# Multimeter_Schematic.net
KiCad netlist of a schematic drawn in Altium Designer
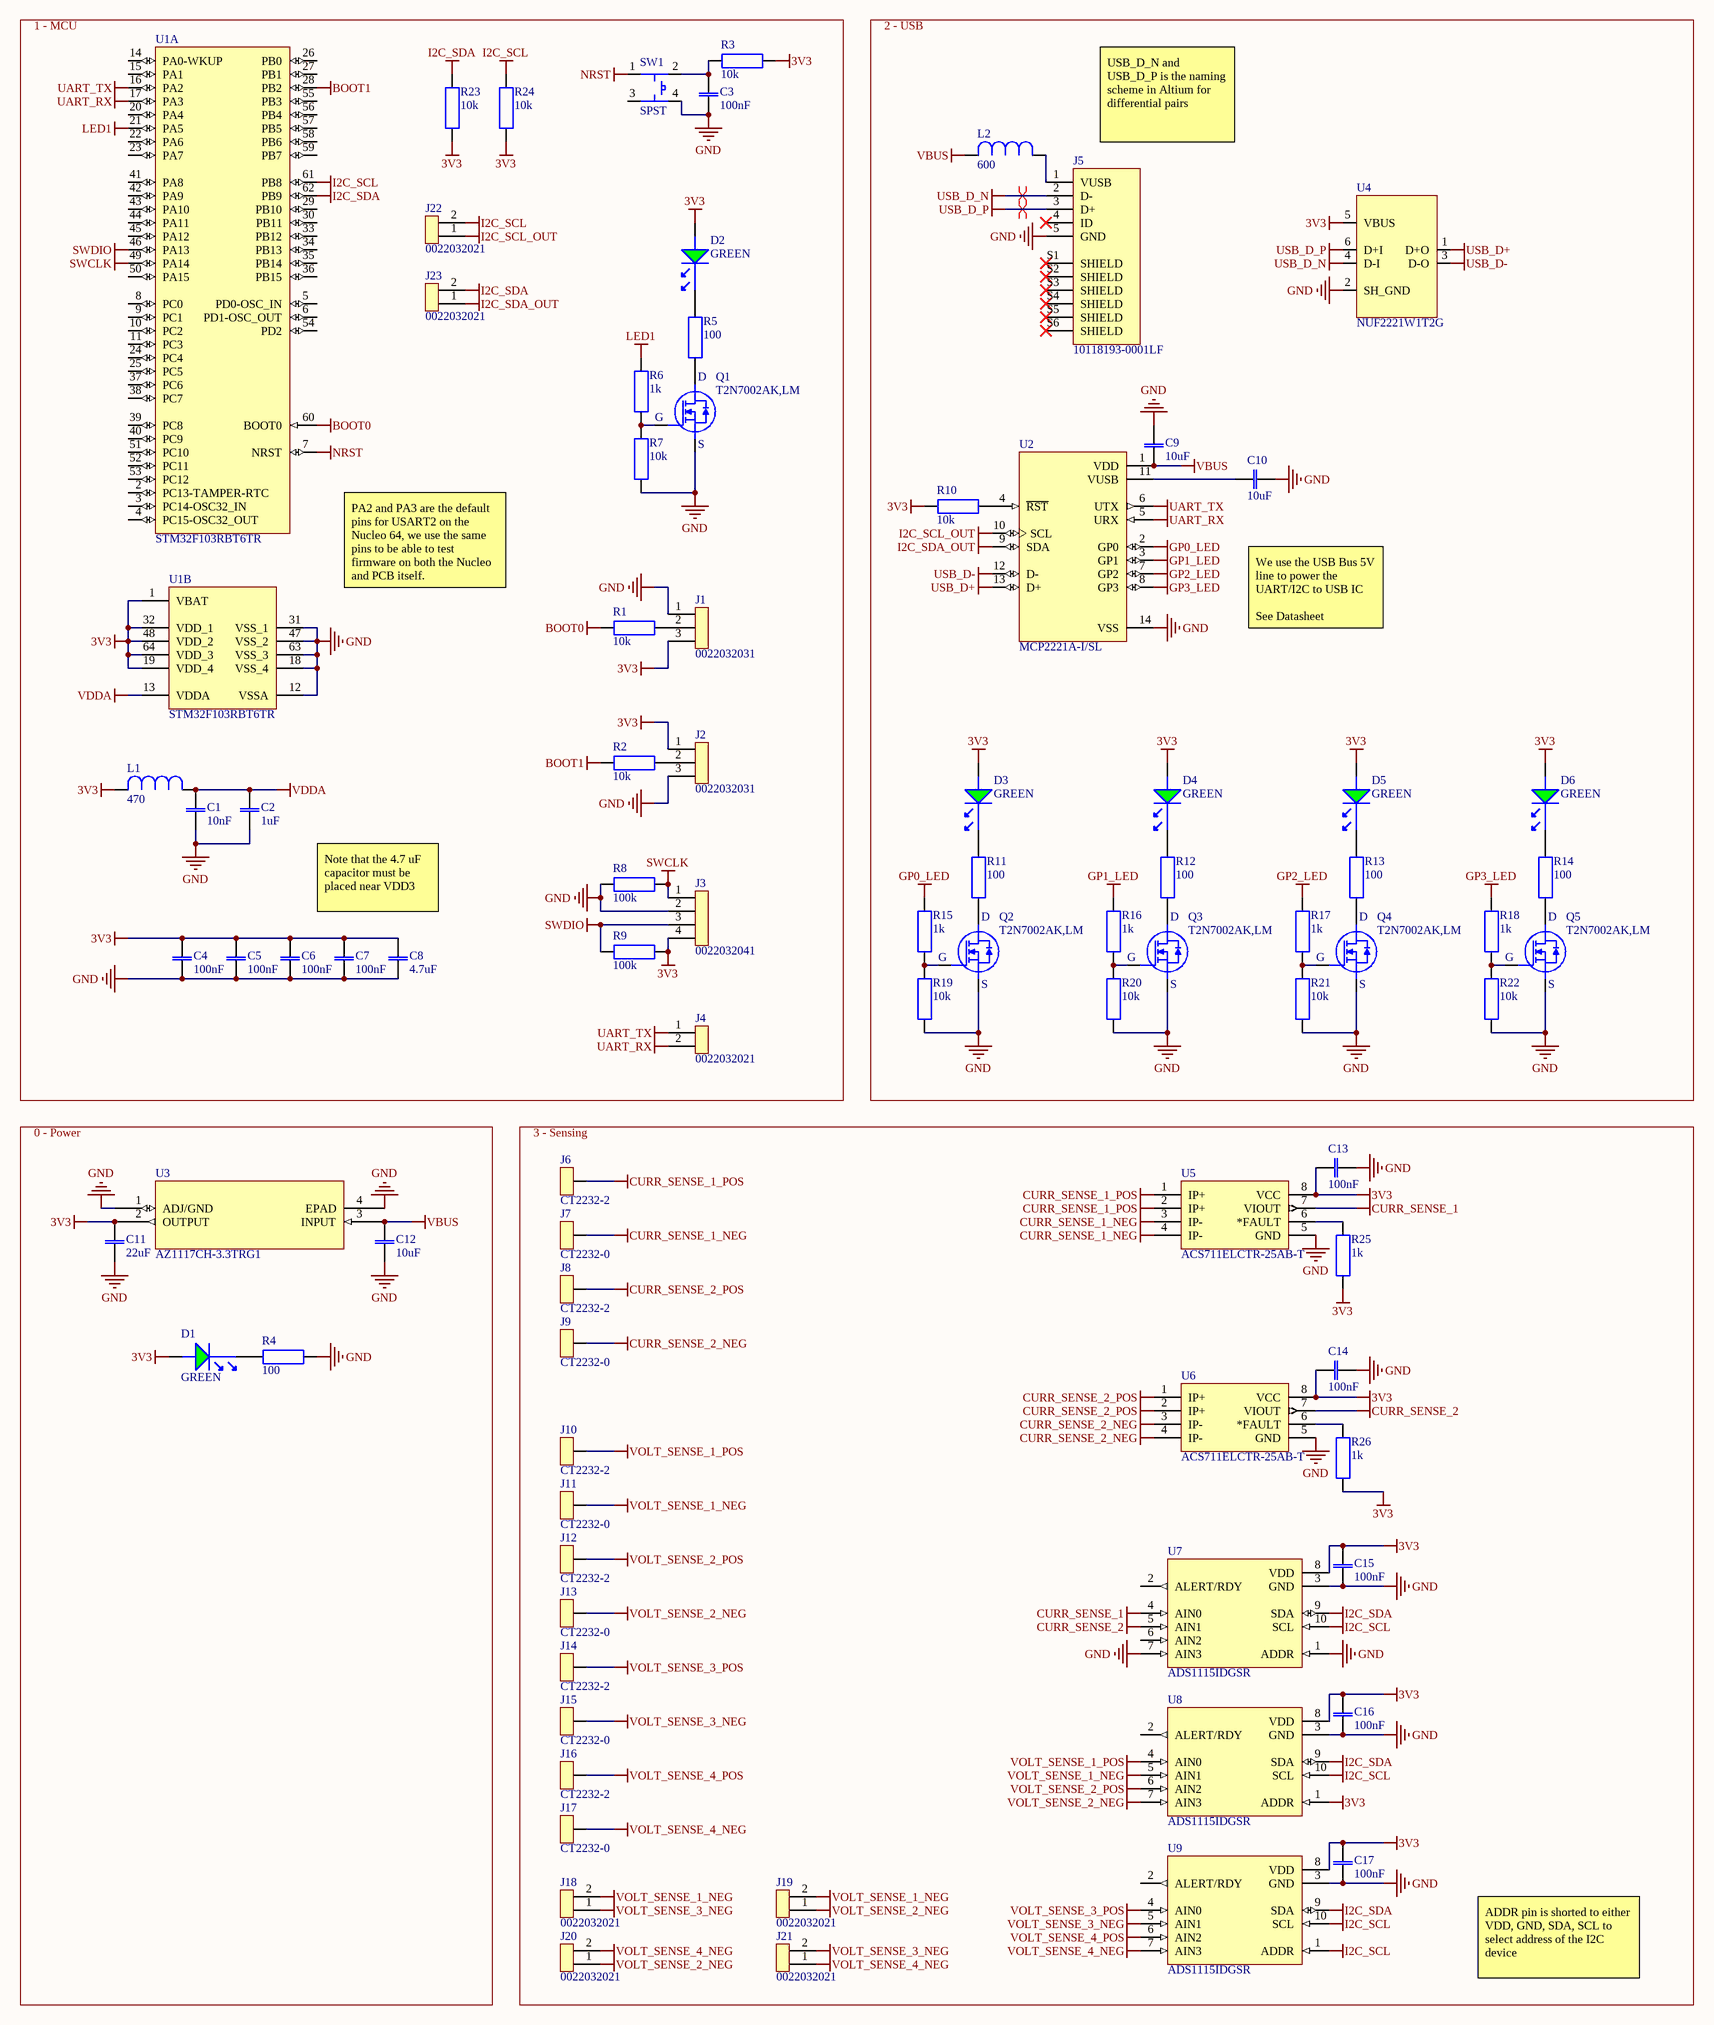
[diagram p0: Multimeter_Schematic.SchDoc]

(export (version "E")
  (design (tool "Eeschema 10.0.6"))
  (components
    (comp (ref "C1")
      (value "10nF")
      (footprint "CAP_CC0805_YAG")
      (description "10000 pF ±10% 25V Ceramic Capacitor X7R 0805 (2012 Metric)")
      (fields
        (field (name "MANUFACTURER") "YAGEO")
        (field (name "MANUFACTURER PART NUMBER") "CC0805KRX7R8BB103")
      )
      (libsource (lib "Multimeter") (part "CC0805KRX7R8BB103"))
    )
    (comp (ref "C2")
      (value "1uF")
      (footprint "CAP_CC0805_YAG")
      (description "1 µF ±10% 25V Ceramic Capacitor X7R 0805 (2012 Metric)")
      (fields
        (field (name "MANUFACTURER") "YAGEO")
        (field (name "MANUFACTURER PART NUMBER") "CC0805KKX7R8BB105")
      )
      (libsource (lib "Multimeter") (part "CC0805KKX7R8BB105"))
    )
    (comp (ref "C3")
      (value "100nF")
      (footprint "CAP_CC0805_YAG")
      (description "0.1 µF ±10% 25V Ceramic Capacitor X7R 0805 (2012 Metric)")
      (fields
        (field (name "MANUFACTURER") "YAGEO")
        (field (name "MANUFACTURER PART NUMBER") "CC0805KRX7R8BB104")
      )
      (libsource (lib "Multimeter") (part "CC0805KRX7R8BB104"))
    )
    (comp (ref "C4")
      (value "100nF")
      (footprint "CAP_CC0805_YAG")
      (description "0.1 µF ±10% 25V Ceramic Capacitor X7R 0805 (2012 Metric)")
      (fields
        (field (name "MANUFACTURER") "YAGEO")
        (field (name "MANUFACTURER PART NUMBER") "CC0805KRX7R8BB104")
      )
      (libsource (lib "Multimeter") (part "CC0805KRX7R8BB104"))
    )
    (comp (ref "C5")
      (value "100nF")
      (footprint "CAP_CC0805_YAG")
      (description "0.1 µF ±10% 25V Ceramic Capacitor X7R 0805 (2012 Metric)")
      (fields
        (field (name "MANUFACTURER") "YAGEO")
        (field (name "MANUFACTURER PART NUMBER") "CC0805KRX7R8BB104")
      )
      (libsource (lib "Multimeter") (part "CC0805KRX7R8BB104"))
    )
    (comp (ref "C6")
      (value "100nF")
      (footprint "CAP_CC0805_YAG")
      (description "0.1 µF ±10% 25V Ceramic Capacitor X7R 0805 (2012 Metric)")
      (fields
        (field (name "MANUFACTURER") "YAGEO")
        (field (name "MANUFACTURER PART NUMBER") "CC0805KRX7R8BB104")
      )
      (libsource (lib "Multimeter") (part "CC0805KRX7R8BB104"))
    )
    (comp (ref "C7")
      (value "100nF")
      (footprint "CAP_CC0805_YAG")
      (description "0.1 µF ±10% 25V Ceramic Capacitor X7R 0805 (2012 Metric)")
      (fields
        (field (name "MANUFACTURER") "YAGEO")
        (field (name "MANUFACTURER PART NUMBER") "CC0805KRX7R8BB104")
      )
      (libsource (lib "Multimeter") (part "CC0805KRX7R8BB104"))
    )
    (comp (ref "C8")
      (value "4.7uF")
      (footprint "CAP_CC0805_YAG")
      (description "4.7 µF ±10% 25V Ceramic Capacitor X7R 0805 (2012 Metric)")
      (fields
        (field (name "MANUFACTURER") "YAGEO")
        (field (name "MANUFACTURER PART NUMBER") "CC0805KKX7R8BB475")
      )
      (libsource (lib "Multimeter") (part "CC0805KKX7R8BB475"))
    )
    (comp (ref "C9")
      (value "10uF")
      (footprint "CAP_CC0805_YAG")
      (description "10 µF ±10% 25V Ceramic Capacitor X5R 0805 (2012 Metric)")
      (fields
        (field (name "MANUFACTURER") "YAGEO")
        (field (name "MANUFACTURER PART NUMBER") "CC0805KKX5R8BB106")
      )
      (libsource (lib "Multimeter") (part "CC0805KKX5R8BB106"))
    )
    (comp (ref "C10")
      (value "10uF")
      (footprint "CAP_CC0805_YAG")
      (description "10 µF ±10% 25V Ceramic Capacitor X5R 0805 (2012 Metric)")
      (fields
        (field (name "MANUFACTURER") "YAGEO")
        (field (name "MANUFACTURER PART NUMBER") "CC0805KKX5R8BB106")
      )
      (libsource (lib "Multimeter") (part "CC0805KKX5R8BB106"))
    )
    (comp (ref "C11")
      (value "22uF")
      (footprint "CAP_CC0805_YAG")
      (description "22 µF ±20% 25V Ceramic Capacitor X5R 0805 (2012 Metric)")
      (fields
        (field (name "MANUFACTURER") "YAGEO")
        (field (name "MANUFACTURER PART NUMBER") "CC0805MKX5R8BB226")
      )
      (libsource (lib "Multimeter") (part "CC0805MKX5R8BB226"))
    )
    (comp (ref "C12")
      (value "10uF")
      (footprint "CAP_CC0805_YAG")
      (description "10 µF ±10% 25V Ceramic Capacitor X5R 0805 (2012 Metric)")
      (fields
        (field (name "MANUFACTURER") "YAGEO")
        (field (name "MANUFACTURER PART NUMBER") "CC0805KKX5R8BB106")
      )
      (libsource (lib "Multimeter") (part "CC0805KKX5R8BB106"))
    )
    (comp (ref "C13")
      (value "100nF")
      (footprint "CAP_CC0805_YAG")
      (description "0.1 µF ±10% 25V Ceramic Capacitor X7R 0805 (2012 Metric)")
      (fields
        (field (name "MANUFACTURER") "YAGEO")
        (field (name "MANUFACTURER PART NUMBER") "CC0805KRX7R8BB104")
      )
      (libsource (lib "Multimeter") (part "CC0805KRX7R8BB104"))
    )
    (comp (ref "C14")
      (value "100nF")
      (footprint "CAP_CC0805_YAG")
      (description "0.1 µF ±10% 25V Ceramic Capacitor X7R 0805 (2012 Metric)")
      (fields
        (field (name "MANUFACTURER") "YAGEO")
        (field (name "MANUFACTURER PART NUMBER") "CC0805KRX7R8BB104")
      )
      (libsource (lib "Multimeter") (part "CC0805KRX7R8BB104"))
    )
    (comp (ref "C15")
      (value "100nF")
      (footprint "CAP_CC0805_YAG")
      (description "0.1 µF ±10% 25V Ceramic Capacitor X7R 0805 (2012 Metric)")
      (fields
        (field (name "MANUFACTURER") "YAGEO")
        (field (name "MANUFACTURER PART NUMBER") "CC0805KRX7R8BB104")
      )
      (libsource (lib "Multimeter") (part "CC0805KRX7R8BB104"))
    )
    (comp (ref "C16")
      (value "100nF")
      (footprint "CAP_CC0805_YAG")
      (description "0.1 µF ±10% 25V Ceramic Capacitor X7R 0805 (2012 Metric)")
      (fields
        (field (name "MANUFACTURER") "YAGEO")
        (field (name "MANUFACTURER PART NUMBER") "CC0805KRX7R8BB104")
      )
      (libsource (lib "Multimeter") (part "CC0805KRX7R8BB104"))
    )
    (comp (ref "C17")
      (value "100nF")
      (footprint "CAP_CC0805_YAG")
      (description "0.1 µF ±10% 25V Ceramic Capacitor X7R 0805 (2012 Metric)")
      (fields
        (field (name "MANUFACTURER") "YAGEO")
        (field (name "MANUFACTURER PART NUMBER") "CC0805KRX7R8BB104")
      )
      (libsource (lib "Multimeter") (part "CC0805KRX7R8BB104"))
    )
    (comp (ref "D1")
      (value "GREEN")
      (footprint "LTST-C170TGKT")
      (description "Green 525nm LED Indication - Discrete 3.2V 0805 (2012 Metric)")
      (fields
        (field (name "MANUFACTURER") "Lite-On Inc.")
        (field (name "MANUFACTURER PART NUMBER") "LTST-C170TGKT")
      )
      (libsource (lib "Multimeter") (part "LTST-C170TGKT"))
    )
    (comp (ref "D2")
      (value "GREEN")
      (footprint "LTST-C170TGKT")
      (description "Green 525nm LED Indication - Discrete 3.2V 0805 (2012 Metric)")
      (fields
        (field (name "MANUFACTURER") "Lite-On Inc.")
        (field (name "MANUFACTURER PART NUMBER") "LTST-C170TGKT")
      )
      (libsource (lib "Multimeter") (part "LTST-C170TGKT"))
    )
    (comp (ref "D3")
      (value "GREEN")
      (footprint "LTST-C170TGKT")
      (description "Green 525nm LED Indication - Discrete 3.2V 0805 (2012 Metric)")
      (fields
        (field (name "MANUFACTURER") "Lite-On Inc.")
        (field (name "MANUFACTURER PART NUMBER") "LTST-C170TGKT")
      )
      (libsource (lib "Multimeter") (part "LTST-C170TGKT"))
    )
    (comp (ref "D4")
      (value "GREEN")
      (footprint "LTST-C170TGKT")
      (description "Green 525nm LED Indication - Discrete 3.2V 0805 (2012 Metric)")
      (fields
        (field (name "MANUFACTURER") "Lite-On Inc.")
        (field (name "MANUFACTURER PART NUMBER") "LTST-C170TGKT")
      )
      (libsource (lib "Multimeter") (part "LTST-C170TGKT"))
    )
    (comp (ref "D5")
      (value "GREEN")
      (footprint "LTST-C170TGKT")
      (description "Green 525nm LED Indication - Discrete 3.2V 0805 (2012 Metric)")
      (fields
        (field (name "MANUFACTURER") "Lite-On Inc.")
        (field (name "MANUFACTURER PART NUMBER") "LTST-C170TGKT")
      )
      (libsource (lib "Multimeter") (part "LTST-C170TGKT"))
    )
    (comp (ref "D6")
      (value "GREEN")
      (footprint "LTST-C170TGKT")
      (description "Green 525nm LED Indication - Discrete 3.2V 0805 (2012 Metric)")
      (fields
        (field (name "MANUFACTURER") "Lite-On Inc.")
        (field (name "MANUFACTURER PART NUMBER") "LTST-C170TGKT")
      )
      (libsource (lib "Multimeter") (part "LTST-C170TGKT"))
    )
    (comp (ref "J1")
      (value "0022032031")
      (footprint "CONN3X1_22032031_MOL")
      (description "Connector Header Through Hole 3 position 0.100\" (2.54mm)")
      (fields (field (name "MANUFACTURER") "Molex"))
      (libsource (lib "Multimeter") (part "0022032031"))
    )
    (comp (ref "J2")
      (value "0022032031")
      (footprint "CONN3X1_22032031_MOL")
      (description "Connector Header Through Hole 3 position 0.100\" (2.54mm)")
      (fields (field (name "MANUFACTURER") "Molex"))
      (libsource (lib "Multimeter") (part "0022032031"))
    )
    (comp (ref "J3")
      (value "0022032041")
      (footprint "CONN3X1_22032041_MOL")
      (description "Connector Header Through Hole 4 position 0.100\" (2.54mm)")
      (fields (field (name "MANUFACTURER") "Molex"))
      (libsource (lib "Multimeter") (part "0022032041"))
    )
    (comp (ref "J4")
      (value "0022032021")
      (footprint "CONN3X1_22032021_MOL")
      (description "Connector Header Through Hole 2 position 0.100\" (2.54mm)")
      (fields (field (name "MANUFACTURER") "Molex"))
      (libsource (lib "Multimeter") (part "0022032021"))
    )
    (comp (ref "J5")
      (value "10118193-0001LF")
      (footprint "AMPHENOL_10118193-0001LF")
      (description "USB - micro B USB 2.0 Receptacle Connector 5 Position Surface Mount, Right Angle; Through Hole")
      (fields (field (name "MF") "Amphenol ICC") (field (name "MANUFACTURER") "Amphenol ICC (FCI)"))
      (libsource (lib "Multimeter") (part "10118193-0001LF"))
    )
    (comp (ref "J6")
      (value "CT2232-2")
      (footprint "CT2232-2")
      (description "(Banana) CONN BIND POST KNURLED RED")
      (fields (field (name "MANUFACTURER") "Cal Test Electronics"))
      (libsource (lib "Multimeter") (part "CT2232-2"))
    )
    (comp (ref "J7")
      (value "CT2232-0")
      (footprint "CT2232-0")
      (description "(Banana) CONN BIND POST KNURLED BLACK")
      (fields (field (name "MANUFACTURER") "Cal Test Electronics"))
      (libsource (lib "Multimeter") (part "CT2232-0"))
    )
    (comp (ref "J8")
      (value "CT2232-2")
      (footprint "CT2232-2")
      (description "(Banana) CONN BIND POST KNURLED RED")
      (fields (field (name "MANUFACTURER") "Cal Test Electronics"))
      (libsource (lib "Multimeter") (part "CT2232-2"))
    )
    (comp (ref "J9")
      (value "CT2232-0")
      (footprint "CT2232-0")
      (description "(Banana) CONN BIND POST KNURLED BLACK")
      (fields (field (name "MANUFACTURER") "Cal Test Electronics"))
      (libsource (lib "Multimeter") (part "CT2232-0"))
    )
    (comp (ref "J10")
      (value "CT2232-2")
      (footprint "CT2232-2")
      (description "(Banana) CONN BIND POST KNURLED RED")
      (fields (field (name "MANUFACTURER") "Cal Test Electronics"))
      (libsource (lib "Multimeter") (part "CT2232-2"))
    )
    (comp (ref "J11")
      (value "CT2232-0")
      (footprint "CT2232-0")
      (description "(Banana) CONN BIND POST KNURLED BLACK")
      (fields (field (name "MANUFACTURER") "Cal Test Electronics"))
      (libsource (lib "Multimeter") (part "CT2232-0"))
    )
    (comp (ref "J12")
      (value "CT2232-2")
      (footprint "CT2232-2")
      (description "(Banana) CONN BIND POST KNURLED RED")
      (fields (field (name "MANUFACTURER") "Cal Test Electronics"))
      (libsource (lib "Multimeter") (part "CT2232-2"))
    )
    (comp (ref "J13")
      (value "CT2232-0")
      (footprint "CT2232-0")
      (description "(Banana) CONN BIND POST KNURLED BLACK")
      (fields (field (name "MANUFACTURER") "Cal Test Electronics"))
      (libsource (lib "Multimeter") (part "CT2232-0"))
    )
    (comp (ref "J14")
      (value "CT2232-2")
      (footprint "CT2232-2")
      (description "(Banana) CONN BIND POST KNURLED RED")
      (fields (field (name "MANUFACTURER") "Cal Test Electronics"))
      (libsource (lib "Multimeter") (part "CT2232-2"))
    )
    (comp (ref "J15")
      (value "CT2232-0")
      (footprint "CT2232-0")
      (description "(Banana) CONN BIND POST KNURLED BLACK")
      (fields (field (name "MANUFACTURER") "Cal Test Electronics"))
      (libsource (lib "Multimeter") (part "CT2232-0"))
    )
    (comp (ref "J16")
      (value "CT2232-2")
      (footprint "CT2232-2")
      (description "(Banana) CONN BIND POST KNURLED RED")
      (fields (field (name "MANUFACTURER") "Cal Test Electronics"))
      (libsource (lib "Multimeter") (part "CT2232-2"))
    )
    (comp (ref "J17")
      (value "CT2232-0")
      (footprint "CT2232-0")
      (description "(Banana) CONN BIND POST KNURLED BLACK")
      (fields (field (name "MANUFACTURER") "Cal Test Electronics"))
      (libsource (lib "Multimeter") (part "CT2232-0"))
    )
    (comp (ref "J18")
      (value "0022032021")
      (footprint "CONN3X1_22032021_MOL")
      (description "Connector Header Through Hole 2 position 0.100\" (2.54mm)")
      (fields (field (name "MANUFACTURER") "Molex"))
      (libsource (lib "") (part "0022032021_1"))
    )
    (comp (ref "J19")
      (value "0022032021")
      (footprint "CONN3X1_22032021_MOL")
      (description "Connector Header Through Hole 2 position 0.100\" (2.54mm)")
      (fields (field (name "MANUFACTURER") "Molex"))
      (libsource (lib "") (part "0022032021_1"))
    )
    (comp (ref "J20")
      (value "0022032021")
      (footprint "CONN3X1_22032021_MOL")
      (description "Connector Header Through Hole 2 position 0.100\" (2.54mm)")
      (fields (field (name "MANUFACTURER") "Molex"))
      (libsource (lib "") (part "0022032021_1"))
    )
    (comp (ref "J21")
      (value "0022032021")
      (footprint "CONN3X1_22032021_MOL")
      (description "Connector Header Through Hole 2 position 0.100\" (2.54mm)")
      (fields (field (name "MANUFACTURER") "Molex"))
      (libsource (lib "") (part "0022032021_1"))
    )
    (comp (ref "J22")
      (value "0022032021")
      (footprint "CONN3X1_22032021_MOL")
      (description "Connector Header Through Hole 2 position 0.100\" (2.54mm)")
      (fields (field (name "MANUFACTURER") "Molex"))
      (libsource (lib "") (part "0022032021_1"))
    )
    (comp (ref "J23")
      (value "0022032021")
      (footprint "CONN3X1_22032021_MOL")
      (description "Connector Header Through Hole 2 position 0.100\" (2.54mm)")
      (fields (field (name "MANUFACTURER") "Molex"))
      (libsource (lib "") (part "0022032021_1"))
    )
    (comp (ref "L1")
      (value "470")
      (footprint "IND_HZ0805G471R-10")
      (description "470 Ohms @ 100 MHz 1 Power, Signal Line Ferrite Bead 0805 (2012 Metric) 1A 200mOhm")
      (fields
        (field (name "MANUFACTURER") "Laird-Signal Integrity Products")
        (field (name "MANUFACTURER PART NUMBER") "HZ0805G471R-10")
      )
      (libsource (lib "Multimeter") (part "HZ0805G471R-10"))
    )
    (comp (ref "L2")
      (value "600")
      (footprint "IND_HZ0805G471R-10")
      (description "600 Ohms @ 100 MHz 1 Power, Signal Line Ferrite Bead 0603 (1608 Metric) 1A 200mOhm")
      (fields
        (field (name "MANUFACTURER") "Laird-Signal Integrity Products")
        (field (name "MANUFACTURER PART NUMBER") "MI0603J601R-10")
      )
      (libsource (lib "Multimeter") (part "MI0603J601R-10"))
    )
    (comp (ref "Q1")
      (value "T2N7002AK,LM")
      (footprint "T2N7002AK,LM")
      (description "N-Channel 60 V 200mA (Ta) 320mW (Ta) Surface Mount SOT-23-3")
      (fields (field (name "MANUFACTURER") "Toshiba Semiconductor and Storage"))
      (libsource (lib "Multimeter") (part "T2N7002AK,LM"))
    )
    (comp (ref "Q2")
      (value "T2N7002AK,LM")
      (footprint "T2N7002AK,LM")
      (description "N-Channel 60 V 200mA (Ta) 320mW (Ta) Surface Mount SOT-23-3")
      (fields (field (name "MANUFACTURER") "Toshiba Semiconductor and Storage"))
      (libsource (lib "Multimeter") (part "T2N7002AK,LM"))
    )
    (comp (ref "Q3")
      (value "T2N7002AK,LM")
      (footprint "T2N7002AK,LM")
      (description "N-Channel 60 V 200mA (Ta) 320mW (Ta) Surface Mount SOT-23-3")
      (fields (field (name "MANUFACTURER") "Toshiba Semiconductor and Storage"))
      (libsource (lib "Multimeter") (part "T2N7002AK,LM"))
    )
    (comp (ref "Q4")
      (value "T2N7002AK,LM")
      (footprint "T2N7002AK,LM")
      (description "N-Channel 60 V 200mA (Ta) 320mW (Ta) Surface Mount SOT-23-3")
      (fields (field (name "MANUFACTURER") "Toshiba Semiconductor and Storage"))
      (libsource (lib "Multimeter") (part "T2N7002AK,LM"))
    )
    (comp (ref "Q5")
      (value "T2N7002AK,LM")
      (footprint "T2N7002AK,LM")
      (description "N-Channel 60 V 200mA (Ta) 320mW (Ta) Surface Mount SOT-23-3")
      (fields (field (name "MANUFACTURER") "Toshiba Semiconductor and Storage"))
      (libsource (lib "Multimeter") (part "T2N7002AK,LM"))
    )
    (comp (ref "R1")
      (value "10k")
      (footprint "RESC2012X60N")
      (description "10 kOhms ±1% 0.125W, 1/8W Chip Resistor 0805 (2012 Metric) Moisture Resistant Thick Film")
      (fields
        (field (name "MANUFACTURER") "YAGEO")
        (field (name "MANUFACTURER PART NUMBER") "RC0805FR-0710KL")
      )
      (libsource (lib "Multimeter") (part "RC0805FR-0710KL"))
    )
    (comp (ref "R2")
      (value "10k")
      (footprint "RESC2012X60N")
      (description "10 kOhms ±1% 0.125W, 1/8W Chip Resistor 0805 (2012 Metric) Moisture Resistant Thick Film")
      (fields
        (field (name "MANUFACTURER") "YAGEO")
        (field (name "MANUFACTURER PART NUMBER") "RC0805FR-0710KL")
      )
      (libsource (lib "Multimeter") (part "RC0805FR-0710KL"))
    )
    (comp (ref "R3")
      (value "10k")
      (footprint "RESC2012X60N")
      (description "10 kOhms ±1% 0.125W, 1/8W Chip Resistor 0805 (2012 Metric) Moisture Resistant Thick Film")
      (fields
        (field (name "MANUFACTURER") "YAGEO")
        (field (name "MANUFACTURER PART NUMBER") "RC0805FR-0710KL")
      )
      (libsource (lib "Multimeter") (part "RC0805FR-0710KL"))
    )
    (comp (ref "R4")
      (value "100")
      (footprint "RESC2012X60N")
      (description "100 Ohms ±1% 0.125W, 1/8W Chip Resistor 0805 (2012 Metric) Moisture Resistant Thick Film")
      (fields
        (field (name "MANUFACTURER") "YAGEO")
        (field (name "MANUFACTURER PART NUMBER") "RC0805FR-07100RL")
      )
      (libsource (lib "Multimeter") (part "RC0805FR-07100RL"))
    )
    (comp (ref "R5")
      (value "100")
      (footprint "RESC2012X60N")
      (description "100 Ohms ±1% 0.125W, 1/8W Chip Resistor 0805 (2012 Metric) Moisture Resistant Thick Film")
      (fields
        (field (name "MANUFACTURER") "YAGEO")
        (field (name "MANUFACTURER PART NUMBER") "RC0805FR-07100RL")
      )
      (libsource (lib "Multimeter") (part "RC0805FR-07100RL"))
    )
    (comp (ref "R6")
      (value "1k")
      (footprint "RESC2012X60N")
      (description "1 kOhms ±1% 0.125W, 1/8W Chip Resistor 0805 (2012 Metric) Moisture Resistant Thick Film")
      (fields
        (field (name "MANUFACTURER") "YAGEO")
        (field (name "MANUFACTURER PART NUMBER") "RC0805FR-071KL")
      )
      (libsource (lib "Multimeter") (part "RC0805FR-071KL"))
    )
    (comp (ref "R7")
      (value "10k")
      (footprint "RESC2012X60N")
      (description "10 kOhms ±1% 0.125W, 1/8W Chip Resistor 0805 (2012 Metric) Moisture Resistant Thick Film")
      (fields
        (field (name "MANUFACTURER") "YAGEO")
        (field (name "MANUFACTURER PART NUMBER") "RC0805FR-0710KL")
      )
      (libsource (lib "Multimeter") (part "RC0805FR-0710KL"))
    )
    (comp (ref "R8")
      (value "100k")
      (footprint "RESC2012X60N")
      (description "100 kOhms ±1% 0.125W, 1/8W Chip Resistor 0805 (2012 Metric) Moisture Resistant Thick Film")
      (fields
        (field (name "MANUFACTURER") "YAGEO")
        (field (name "MANUFACTURER PART NUMBER") "RC0805FR-07100KL")
      )
      (libsource (lib "Multimeter") (part "RC0805FR-07100KL"))
    )
    (comp (ref "R9")
      (value "100k")
      (footprint "RESC2012X60N")
      (description "100 kOhms ±1% 0.125W, 1/8W Chip Resistor 0805 (2012 Metric) Moisture Resistant Thick Film")
      (fields
        (field (name "MANUFACTURER") "YAGEO")
        (field (name "MANUFACTURER PART NUMBER") "RC0805FR-07100KL")
      )
      (libsource (lib "Multimeter") (part "RC0805FR-07100KL"))
    )
    (comp (ref "R10")
      (value "10k")
      (footprint "RESC2012X60N")
      (description "10 kOhms ±1% 0.125W, 1/8W Chip Resistor 0805 (2012 Metric) Moisture Resistant Thick Film")
      (fields
        (field (name "MANUFACTURER") "YAGEO")
        (field (name "MANUFACTURER PART NUMBER") "RC0805FR-0710KL")
      )
      (libsource (lib "Multimeter") (part "RC0805FR-0710KL"))
    )
    (comp (ref "R11")
      (value "100")
      (footprint "RESC2012X60N")
      (description "100 Ohms ±1% 0.125W, 1/8W Chip Resistor 0805 (2012 Metric) Moisture Resistant Thick Film")
      (fields
        (field (name "MANUFACTURER") "YAGEO")
        (field (name "MANUFACTURER PART NUMBER") "RC0805FR-07100RL")
      )
      (libsource (lib "Multimeter") (part "RC0805FR-07100RL"))
    )
    (comp (ref "R12")
      (value "100")
      (footprint "RESC2012X60N")
      (description "100 Ohms ±1% 0.125W, 1/8W Chip Resistor 0805 (2012 Metric) Moisture Resistant Thick Film")
      (fields
        (field (name "MANUFACTURER") "YAGEO")
        (field (name "MANUFACTURER PART NUMBER") "RC0805FR-07100RL")
      )
      (libsource (lib "Multimeter") (part "RC0805FR-07100RL"))
    )
    (comp (ref "R13")
      (value "100")
      (footprint "RESC2012X60N")
      (description "100 Ohms ±1% 0.125W, 1/8W Chip Resistor 0805 (2012 Metric) Moisture Resistant Thick Film")
      (fields
        (field (name "MANUFACTURER") "YAGEO")
        (field (name "MANUFACTURER PART NUMBER") "RC0805FR-07100RL")
      )
      (libsource (lib "Multimeter") (part "RC0805FR-07100RL"))
    )
    (comp (ref "R14")
      (value "100")
      (footprint "RESC2012X60N")
      (description "100 Ohms ±1% 0.125W, 1/8W Chip Resistor 0805 (2012 Metric) Moisture Resistant Thick Film")
      (fields
        (field (name "MANUFACTURER") "YAGEO")
        (field (name "MANUFACTURER PART NUMBER") "RC0805FR-07100RL")
      )
      (libsource (lib "Multimeter") (part "RC0805FR-07100RL"))
    )
    (comp (ref "R15")
      (value "1k")
      (footprint "RESC2012X60N")
      (description "1 kOhms ±1% 0.125W, 1/8W Chip Resistor 0805 (2012 Metric) Moisture Resistant Thick Film")
      (fields
        (field (name "MANUFACTURER") "YAGEO")
        (field (name "MANUFACTURER PART NUMBER") "RC0805FR-071KL")
      )
      (libsource (lib "Multimeter") (part "RC0805FR-071KL"))
    )
    (comp (ref "R16")
      (value "1k")
      (footprint "RESC2012X60N")
      (description "1 kOhms ±1% 0.125W, 1/8W Chip Resistor 0805 (2012 Metric) Moisture Resistant Thick Film")
      (fields
        (field (name "MANUFACTURER") "YAGEO")
        (field (name "MANUFACTURER PART NUMBER") "RC0805FR-071KL")
      )
      (libsource (lib "Multimeter") (part "RC0805FR-071KL"))
    )
    (comp (ref "R17")
      (value "1k")
      (footprint "RESC2012X60N")
      (description "1 kOhms ±1% 0.125W, 1/8W Chip Resistor 0805 (2012 Metric) Moisture Resistant Thick Film")
      (fields
        (field (name "MANUFACTURER") "YAGEO")
        (field (name "MANUFACTURER PART NUMBER") "RC0805FR-071KL")
      )
      (libsource (lib "Multimeter") (part "RC0805FR-071KL"))
    )
    (comp (ref "R18")
      (value "1k")
      (footprint "RESC2012X60N")
      (description "1 kOhms ±1% 0.125W, 1/8W Chip Resistor 0805 (2012 Metric) Moisture Resistant Thick Film")
      (fields
        (field (name "MANUFACTURER") "YAGEO")
        (field (name "MANUFACTURER PART NUMBER") "RC0805FR-071KL")
      )
      (libsource (lib "Multimeter") (part "RC0805FR-071KL"))
    )
    (comp (ref "R19")
      (value "10k")
      (footprint "RESC2012X60N")
      (description "10 kOhms ±1% 0.125W, 1/8W Chip Resistor 0805 (2012 Metric) Moisture Resistant Thick Film")
      (fields
        (field (name "MANUFACTURER") "YAGEO")
        (field (name "MANUFACTURER PART NUMBER") "RC0805FR-0710KL")
      )
      (libsource (lib "Multimeter") (part "RC0805FR-0710KL"))
    )
    (comp (ref "R20")
      (value "10k")
      (footprint "RESC2012X60N")
      (description "10 kOhms ±1% 0.125W, 1/8W Chip Resistor 0805 (2012 Metric) Moisture Resistant Thick Film")
      (fields
        (field (name "MANUFACTURER") "YAGEO")
        (field (name "MANUFACTURER PART NUMBER") "RC0805FR-0710KL")
      )
      (libsource (lib "Multimeter") (part "RC0805FR-0710KL"))
    )
    (comp (ref "R21")
      (value "10k")
      (footprint "RESC2012X60N")
      (description "10 kOhms ±1% 0.125W, 1/8W Chip Resistor 0805 (2012 Metric) Moisture Resistant Thick Film")
      (fields
        (field (name "MANUFACTURER") "YAGEO")
        (field (name "MANUFACTURER PART NUMBER") "RC0805FR-0710KL")
      )
      (libsource (lib "Multimeter") (part "RC0805FR-0710KL"))
    )
    (comp (ref "R22")
      (value "10k")
      (footprint "RESC2012X60N")
      (description "10 kOhms ±1% 0.125W, 1/8W Chip Resistor 0805 (2012 Metric) Moisture Resistant Thick Film")
      (fields
        (field (name "MANUFACTURER") "YAGEO")
        (field (name "MANUFACTURER PART NUMBER") "RC0805FR-0710KL")
      )
      (libsource (lib "Multimeter") (part "RC0805FR-0710KL"))
    )
    (comp (ref "R23")
      (value "10k")
      (footprint "RESC2012X60N")
      (description "10 kOhms ±1% 0.125W, 1/8W Chip Resistor 0805 (2012 Metric) Moisture Resistant Thick Film")
      (fields
        (field (name "MANUFACTURER") "YAGEO")
        (field (name "MANUFACTURER PART NUMBER") "RC0805FR-0710KL")
      )
      (libsource (lib "Multimeter") (part "RC0805FR-0710KL"))
    )
    (comp (ref "R24")
      (value "10k")
      (footprint "RESC2012X60N")
      (description "10 kOhms ±1% 0.125W, 1/8W Chip Resistor 0805 (2012 Metric) Moisture Resistant Thick Film")
      (fields
        (field (name "MANUFACTURER") "YAGEO")
        (field (name "MANUFACTURER PART NUMBER") "RC0805FR-0710KL")
      )
      (libsource (lib "Multimeter") (part "RC0805FR-0710KL"))
    )
    (comp (ref "R25")
      (value "1k")
      (footprint "RESC2012X60N")
      (description "1 kOhms ±1% 0.125W, 1/8W Chip Resistor 0805 (2012 Metric) Moisture Resistant Thick Film")
      (fields
        (field (name "MANUFACTURER") "YAGEO")
        (field (name "MANUFACTURER PART NUMBER") "RC0805FR-071KL")
      )
      (libsource (lib "Multimeter") (part "RC0805FR-071KL"))
    )
    (comp (ref "R26")
      (value "1k")
      (footprint "RESC2012X60N")
      (description "1 kOhms ±1% 0.125W, 1/8W Chip Resistor 0805 (2012 Metric) Moisture Resistant Thick Film")
      (fields
        (field (name "MANUFACTURER") "YAGEO")
        (field (name "MANUFACTURER PART NUMBER") "RC0805FR-071KL")
      )
      (libsource (lib "Multimeter") (part "RC0805FR-071KL"))
    )
    (comp (ref "SW1")
      (value "SPST")
      (footprint "SW4-SMD-5.2X5.2X1.5MM")
      (description "Tactile Switch SPST-NO Top Actuated Surface Mount")
      (fields (field (name "MANUFACTURER") "Alps Alpine"))
      (libsource (lib "Multimeter") (part "SPST"))
    )
    (comp (ref "U1")
      (value "STM32F103RBT6TR")
      (footprint "STM-LQFP64_V")
      (libsource (lib "Multimeter") (part "CMP-0237-00169-4"))
    )
    (comp (ref "U2")
      (value "MCP2221A-I/SL")
      (footprint "SOIC127P600X175-14N")
      (description "USB Bridge, USB to I2C/UART USB 2.0 I2C, UART Interface 14-SOIC")
      (fields (field (name "MANUFACTURER") "Microchip Technology"))
      (libsource (lib "Multimeter") (part "MCP2221A-I/SL"))
    )
    (comp (ref "U3")
      (value "AZ1117CH-3.3TRG1")
      (footprint "SOT-223_DIO")
      (description "Linear Voltage Regulator IC Positive Fixed 1 Output 1A SOT-223-3")
      (fields (field (name "MANUFACTURER") "Diodes Incorporated"))
      (libsource (lib "Multimeter") (part "AZ1117CH-3.3TRG1"))
    )
    (comp (ref "U4")
      (value "NUF2221W1T2G")
      (footprint "SOT-363")
      (fields (field (name "MANUFACTURER") "onsemi"))
      (libsource (lib "Multimeter") (part "NUF2221W1T2G"))
    )
    (comp (ref "U5")
      (value "ACS711ELCTR-25AB-T")
      (footprint "SOICN-8_ALM")
      (description "Current Sensor 25A 1 Channel Hall Effect, Open Loop Bidirectional 8-SOIC (0.154\", 3.90mm Width)")
      (fields (field (name "MANUFACTURER") "*Allegro MicroSystems"))
      (libsource (lib "Multimeter") (part "ACS711ELCTR-25AB-T"))
    )
    (comp (ref "U6")
      (value "ACS711ELCTR-25AB-T")
      (footprint "SOICN-8_ALM")
      (description "Current Sensor 25A 1 Channel Hall Effect, Open Loop Bidirectional 8-SOIC (0.154\", 3.90mm Width)")
      (fields (field (name "MANUFACTURER") "*Allegro MicroSystems"))
      (libsource (lib "Multimeter") (part "ACS711ELCTR-25AB-T"))
    )
    (comp (ref "U7")
      (value "ADS1115IDGSR")
      (footprint "SOP50P490X110-10N")
      (description "16 Bit Analog to Digital Converter 2, 4 Input 1 Sigma-Delta 10-VSSOP")
      (fields (field (name "MANUFACTURER") "Texas Instruments"))
      (libsource (lib "Multimeter") (part "ADS1115IDGSR"))
    )
    (comp (ref "U8")
      (value "ADS1115IDGSR")
      (footprint "SOP50P490X110-10N")
      (description "16 Bit Analog to Digital Converter 2, 4 Input 1 Sigma-Delta 10-VSSOP")
      (fields (field (name "MANUFACTURER") "Texas Instruments"))
      (libsource (lib "Multimeter") (part "ADS1115IDGSR"))
    )
    (comp (ref "U9")
      (value "ADS1115IDGSR")
      (footprint "SOP50P490X110-10N")
      (description "16 Bit Analog to Digital Converter 2, 4 Input 1 Sigma-Delta 10-VSSOP")
      (fields (field (name "MANUFACTURER") "Texas Instruments"))
      (libsource (lib "Multimeter") (part "ADS1115IDGSR"))
    )
  )
  (nets
    (net (code "1") (name "3V3") (class "Default")
      (node (ref "C11") (pin "2") (pinfunction "2_2") (pintype "passive"))
      (node (ref "C13") (pin "2") (pinfunction "2_2") (pintype "passive"))
      (node (ref "C14") (pin "2") (pinfunction "2_2") (pintype "passive"))
      (node (ref "C15") (pin "2") (pinfunction "2_2") (pintype "passive"))
      (node (ref "C16") (pin "2") (pinfunction "2_2") (pintype "passive"))
      (node (ref "C17") (pin "2") (pinfunction "2_2") (pintype "passive"))
      (node (ref "C4") (pin "2") (pinfunction "2_2") (pintype "passive"))
      (node (ref "C5") (pin "1") (pinfunction "1_1") (pintype "passive"))
      (node (ref "C6") (pin "1") (pinfunction "1_1") (pintype "passive"))
      (node (ref "C7") (pin "1") (pinfunction "1_1") (pintype "passive"))
      (node (ref "C8") (pin "2") (pinfunction "2_2") (pintype "passive"))
      (node (ref "D1") (pin "1") (pintype "passive"))
      (node (ref "D2") (pin "1") (pintype "passive"))
      (node (ref "D3") (pin "1") (pintype "passive"))
      (node (ref "D4") (pin "1") (pintype "passive"))
      (node (ref "D5") (pin "1") (pintype "passive"))
      (node (ref "D6") (pin "1") (pintype "passive"))
      (node (ref "J1") (pin "3") (pinfunction "3_3") (pintype "passive"))
      (node (ref "J2") (pin "1") (pinfunction "1_1") (pintype "passive"))
      (node (ref "J3") (pin "4") (pinfunction "4_4") (pintype "passive"))
      (node (ref "L1") (pin "2") (pinfunction "2_2") (pintype "passive"))
      (node (ref "R10") (pin "1") (pintype "passive"))
      (node (ref "R23") (pin "2") (pintype "passive"))
      (node (ref "R24") (pin "1") (pintype "passive"))
      (node (ref "R25") (pin "1") (pintype "passive"))
      (node (ref "R26") (pin "1") (pintype "passive"))
      (node (ref "R3") (pin "2") (pintype "passive"))
      (node (ref "R9") (pin "1") (pintype "passive"))
      (node (ref "U1") (pin "1") (pinfunction "VBAT_1") (pintype "power_in"))
      (node (ref "U1") (pin "19") (pinfunction "VDD_4_19") (pintype "power_in"))
      (node (ref "U1") (pin "32") (pinfunction "VDD_1_32") (pintype "power_in"))
      (node (ref "U1") (pin "48") (pinfunction "VDD_2_48") (pintype "power_in"))
      (node (ref "U1") (pin "64") (pinfunction "VDD_3_64") (pintype "power_in"))
      (node (ref "U3") (pin "2") (pinfunction "OUTPUT_2") (pintype "output"))
      (node (ref "U4") (pin "5") (pinfunction "VBUS_5") (pintype "power_in"))
      (node (ref "U5") (pin "8") (pinfunction "VCC_8") (pintype "power_in"))
      (node (ref "U6") (pin "8") (pinfunction "VCC_8") (pintype "power_in"))
      (node (ref "U7") (pin "8") (pinfunction "VDD_8") (pintype "power_in"))
      (node (ref "U8") (pin "1") (pinfunction "ADDR_1") (pintype "input"))
      (node (ref "U8") (pin "8") (pinfunction "VDD_8") (pintype "power_in"))
      (node (ref "U9") (pin "8") (pinfunction "VDD_8") (pintype "power_in"))
    )
    (net (code "2") (name "BOOT0") (class "Default")
      (node (ref "R1") (pin "1") (pintype "passive"))
      (node (ref "U1") (pin "60") (pinfunction "BOOT0_60") (pintype "input"))
    )
    (net (code "3") (name "BOOT1") (class "Default")
      (node (ref "R2") (pin "1") (pintype "passive"))
      (node (ref "U1") (pin "28") (pinfunction "PB2_28") (pintype "bidirectional"))
    )
    (net (code "4") (name "CURR_SENSE_1") (class "Default")
      (node (ref "U5") (pin "7") (pinfunction "VIOUT_7") (pintype "output"))
      (node (ref "U7") (pin "4") (pinfunction "AIN0_4") (pintype "input"))
    )
    (net (code "5") (name "CURR_SENSE_1_NEG") (class "Default")
      (node (ref "J7") (pin "1") (pintype "passive"))
      (node (ref "U5") (pin "3") (pinfunction "IP-_3") (pintype "passive"))
      (node (ref "U5") (pin "4") (pinfunction "IP-_4") (pintype "passive"))
    )
    (net (code "6") (name "CURR_SENSE_1_POS") (class "Default")
      (node (ref "J6") (pin "1") (pintype "passive"))
      (node (ref "U5") (pin "1") (pinfunction "IP+_1") (pintype "passive"))
      (node (ref "U5") (pin "2") (pinfunction "IP+_2") (pintype "passive"))
    )
    (net (code "7") (name "CURR_SENSE_2") (class "Default")
      (node (ref "U6") (pin "7") (pinfunction "VIOUT_7") (pintype "output"))
      (node (ref "U7") (pin "5") (pinfunction "AIN1_5") (pintype "input"))
    )
    (net (code "8") (name "CURR_SENSE_2_NEG") (class "Default")
      (node (ref "J9") (pin "1") (pintype "passive"))
      (node (ref "U6") (pin "3") (pinfunction "IP-_3") (pintype "passive"))
      (node (ref "U6") (pin "4") (pinfunction "IP-_4") (pintype "passive"))
    )
    (net (code "9") (name "CURR_SENSE_2_POS") (class "Default")
      (node (ref "J8") (pin "1") (pintype "passive"))
      (node (ref "U6") (pin "1") (pinfunction "IP+_1") (pintype "passive"))
      (node (ref "U6") (pin "2") (pinfunction "IP+_2") (pintype "passive"))
    )
    (net (code "10") (name "GND") (class "Default")
      (node (ref "C1") (pin "1") (pinfunction "1_1") (pintype "passive"))
      (node (ref "C10") (pin "2") (pinfunction "2_2") (pintype "passive"))
      (node (ref "C11") (pin "1") (pinfunction "1_1") (pintype "passive"))
      (node (ref "C12") (pin "1") (pinfunction "1_1") (pintype "passive"))
      (node (ref "C13") (pin "1") (pinfunction "1_1") (pintype "passive"))
      (node (ref "C14") (pin "1") (pinfunction "1_1") (pintype "passive"))
      (node (ref "C15") (pin "1") (pinfunction "1_1") (pintype "passive"))
      (node (ref "C16") (pin "1") (pinfunction "1_1") (pintype "passive"))
      (node (ref "C17") (pin "1") (pinfunction "1_1") (pintype "passive"))
      (node (ref "C2") (pin "1") (pinfunction "1_1") (pintype "passive"))
      (node (ref "C3") (pin "1") (pinfunction "1_1") (pintype "passive"))
      (node (ref "C4") (pin "1") (pinfunction "1_1") (pintype "passive"))
      (node (ref "C5") (pin "2") (pinfunction "2_2") (pintype "passive"))
      (node (ref "C6") (pin "2") (pinfunction "2_2") (pintype "passive"))
      (node (ref "C7") (pin "2") (pinfunction "2_2") (pintype "passive"))
      (node (ref "C8") (pin "1") (pinfunction "1_1") (pintype "passive"))
      (node (ref "C9") (pin "2") (pinfunction "2_2") (pintype "passive"))
      (node (ref "J1") (pin "1") (pinfunction "1_1") (pintype "passive"))
      (node (ref "J2") (pin "3") (pinfunction "3_3") (pintype "passive"))
      (node (ref "J3") (pin "2") (pinfunction "2_2") (pintype "passive"))
      (node (ref "J5") (pin "5") (pinfunction "GND_5") (pintype "passive"))
      (node (ref "Q1") (pin "2") (pintype "passive"))
      (node (ref "Q2") (pin "2") (pintype "passive"))
      (node (ref "Q3") (pin "2") (pintype "passive"))
      (node (ref "Q4") (pin "2") (pintype "passive"))
      (node (ref "Q5") (pin "2") (pintype "passive"))
      (node (ref "R19") (pin "1") (pintype "passive"))
      (node (ref "R20") (pin "1") (pintype "passive"))
      (node (ref "R21") (pin "1") (pintype "passive"))
      (node (ref "R22") (pin "1") (pintype "passive"))
      (node (ref "R4") (pin "1") (pintype "passive"))
      (node (ref "R7") (pin "1") (pintype "passive"))
      (node (ref "R8") (pin "2") (pintype "passive"))
      (node (ref "SW1") (pin "4") (pintype "passive"))
      (node (ref "U1") (pin "12") (pinfunction "VSSA_12") (pintype "power_in"))
      (node (ref "U1") (pin "18") (pinfunction "VSS_4_18") (pintype "power_in"))
      (node (ref "U1") (pin "31") (pinfunction "VSS_1_31") (pintype "power_in"))
      (node (ref "U1") (pin "47") (pinfunction "VSS_2_47") (pintype "power_in"))
      (node (ref "U1") (pin "63") (pinfunction "VSS_3_63") (pintype "power_in"))
      (node (ref "U2") (pin "14") (pinfunction "VSS_14") (pintype "power_in"))
      (node (ref "U3") (pin "1") (pinfunction "ADJ/GND_1") (pintype "bidirectional"))
      (node (ref "U3") (pin "4") (pinfunction "EPAD_4") (pintype "passive"))
      (node (ref "U4") (pin "2") (pinfunction "SH_GND_2") (pintype "power_in"))
      (node (ref "U5") (pin "5") (pinfunction "GND_5") (pintype "power_in"))
      (node (ref "U6") (pin "5") (pinfunction "GND_5") (pintype "power_in"))
      (node (ref "U7") (pin "1") (pinfunction "ADDR_1") (pintype "input"))
      (node (ref "U7") (pin "3") (pinfunction "GND_3") (pintype "power_in"))
      (node (ref "U7") (pin "7") (pinfunction "AIN3_7") (pintype "input"))
      (node (ref "U8") (pin "3") (pinfunction "GND_3") (pintype "power_in"))
      (node (ref "U9") (pin "3") (pinfunction "GND_3") (pintype "power_in"))
    )
    (net (code "11") (name "GP0_LED") (class "Default")
      (node (ref "R15") (pin "2") (pintype "passive"))
      (node (ref "U2") (pin "2") (pinfunction "GP0_2") (pintype "bidirectional"))
    )
    (net (code "12") (name "GP1_LED") (class "Default")
      (node (ref "R16") (pin "2") (pintype "passive"))
      (node (ref "U2") (pin "3") (pinfunction "GP1_3") (pintype "bidirectional"))
    )
    (net (code "13") (name "GP2_LED") (class "Default")
      (node (ref "R17") (pin "2") (pintype "passive"))
      (node (ref "U2") (pin "7") (pinfunction "GP2_7") (pintype "bidirectional"))
    )
    (net (code "14") (name "GP3_LED") (class "Default")
      (node (ref "R18") (pin "2") (pintype "passive"))
      (node (ref "U2") (pin "8") (pinfunction "GP3_8") (pintype "bidirectional"))
    )
    (net (code "15") (name "I2C_SCL") (class "Default")
      (node (ref "J22") (pin "2") (pinfunction "2_2") (pintype "passive"))
      (node (ref "R24") (pin "2") (pintype "passive"))
      (node (ref "U1") (pin "61") (pinfunction "PB8_61") (pintype "bidirectional"))
      (node (ref "U7") (pin "10") (pinfunction "SCL_10") (pintype "input"))
      (node (ref "U8") (pin "10") (pinfunction "SCL_10") (pintype "input"))
      (node (ref "U9") (pin "1") (pinfunction "ADDR_1") (pintype "input"))
      (node (ref "U9") (pin "10") (pinfunction "SCL_10") (pintype "input"))
    )
    (net (code "16") (name "I2C_SCL_OUT") (class "Default")
      (node (ref "J22") (pin "1") (pinfunction "1_1") (pintype "passive"))
      (node (ref "U2") (pin "10") (pinfunction "SCL_10") (pintype "bidirectional"))
    )
    (net (code "17") (name "I2C_SDA") (class "Default")
      (node (ref "J23") (pin "2") (pinfunction "2_2") (pintype "passive"))
      (node (ref "R23") (pin "1") (pintype "passive"))
      (node (ref "U1") (pin "62") (pinfunction "PB9_62") (pintype "bidirectional"))
      (node (ref "U7") (pin "9") (pinfunction "SDA_9") (pintype "bidirectional"))
      (node (ref "U8") (pin "9") (pinfunction "SDA_9") (pintype "bidirectional"))
      (node (ref "U9") (pin "9") (pinfunction "SDA_9") (pintype "bidirectional"))
    )
    (net (code "18") (name "I2C_SDA_OUT") (class "Default")
      (node (ref "J23") (pin "1") (pinfunction "1_1") (pintype "passive"))
      (node (ref "U2") (pin "9") (pinfunction "SDA_9") (pintype "bidirectional"))
    )
    (net (code "19") (name "LED1") (class "Default")
      (node (ref "R6") (pin "2") (pintype "passive"))
      (node (ref "U1") (pin "21") (pinfunction "PA5_21") (pintype "bidirectional"))
    )
    (net (code "20") (name "NRST") (class "Default")
      (node (ref "SW1") (pin "1") (pintype "passive"))
      (node (ref "U1") (pin "7") (pinfunction "NRST_7") (pintype "bidirectional"))
    )
    (net (code "21") (name "Net-(C3-Pad2)") (class "Default")
      (node (ref "C3") (pin "2") (pinfunction "2_2") (pintype "passive"))
      (node (ref "R3") (pin "1") (pintype "passive"))
      (node (ref "SW1") (pin "2") (pintype "passive"))
    )
    (net (code "22") (name "Net-(D1-Pad2)") (class "Default")
      (node (ref "D1") (pin "2") (pintype "passive"))
      (node (ref "R4") (pin "2") (pintype "passive"))
    )
    (net (code "23") (name "Net-(D2-Pad2)") (class "Default")
      (node (ref "D2") (pin "2") (pintype "passive"))
      (node (ref "R5") (pin "2") (pintype "passive"))
    )
    (net (code "24") (name "Net-(D3-Pad2)") (class "Default")
      (node (ref "D3") (pin "2") (pintype "passive"))
      (node (ref "R11") (pin "2") (pintype "passive"))
    )
    (net (code "25") (name "Net-(D4-Pad2)") (class "Default")
      (node (ref "D4") (pin "2") (pintype "passive"))
      (node (ref "R12") (pin "2") (pintype "passive"))
    )
    (net (code "26") (name "Net-(D5-Pad2)") (class "Default")
      (node (ref "D5") (pin "2") (pintype "passive"))
      (node (ref "R13") (pin "2") (pintype "passive"))
    )
    (net (code "27") (name "Net-(D6-Pad2)") (class "Default")
      (node (ref "D6") (pin "2") (pintype "passive"))
      (node (ref "R14") (pin "2") (pintype "passive"))
    )
    (net (code "28") (name "Net-(J1-Pad2)") (class "Default")
      (node (ref "J1") (pin "2") (pinfunction "2_2") (pintype "passive"))
      (node (ref "R1") (pin "2") (pintype "passive"))
    )
    (net (code "29") (name "Net-(J2-Pad2)") (class "Default")
      (node (ref "J2") (pin "2") (pinfunction "2_2") (pintype "passive"))
      (node (ref "R2") (pin "2") (pintype "passive"))
    )
    (net (code "30") (name "Net-(J5-VUSB)") (class "Default")
      (node (ref "J5") (pin "1") (pinfunction "VUSB_1") (pintype "passive"))
      (node (ref "L2") (pin "1") (pinfunction "1_1") (pintype "passive"))
    )
    (net (code "31") (name "Net-(Q1-Pad1)") (class "Default")
      (node (ref "Q1") (pin "1") (pintype "passive"))
      (node (ref "R6") (pin "1") (pintype "passive"))
      (node (ref "R7") (pin "2") (pintype "passive"))
    )
    (net (code "32") (name "Net-(Q1-Pad3)") (class "Default")
      (node (ref "Q1") (pin "3") (pintype "passive"))
      (node (ref "R5") (pin "1") (pintype "passive"))
    )
    (net (code "33") (name "Net-(Q2-Pad1)") (class "Default")
      (node (ref "Q2") (pin "1") (pintype "passive"))
      (node (ref "R15") (pin "1") (pintype "passive"))
      (node (ref "R19") (pin "2") (pintype "passive"))
    )
    (net (code "34") (name "Net-(Q2-Pad3)") (class "Default")
      (node (ref "Q2") (pin "3") (pintype "passive"))
      (node (ref "R11") (pin "1") (pintype "passive"))
    )
    (net (code "35") (name "Net-(Q3-Pad1)") (class "Default")
      (node (ref "Q3") (pin "1") (pintype "passive"))
      (node (ref "R16") (pin "1") (pintype "passive"))
      (node (ref "R20") (pin "2") (pintype "passive"))
    )
    (net (code "36") (name "Net-(Q3-Pad3)") (class "Default")
      (node (ref "Q3") (pin "3") (pintype "passive"))
      (node (ref "R12") (pin "1") (pintype "passive"))
    )
    (net (code "37") (name "Net-(Q4-Pad1)") (class "Default")
      (node (ref "Q4") (pin "1") (pintype "passive"))
      (node (ref "R17") (pin "1") (pintype "passive"))
      (node (ref "R21") (pin "2") (pintype "passive"))
    )
    (net (code "38") (name "Net-(Q4-Pad3)") (class "Default")
      (node (ref "Q4") (pin "3") (pintype "passive"))
      (node (ref "R13") (pin "1") (pintype "passive"))
    )
    (net (code "39") (name "Net-(Q5-Pad1)") (class "Default")
      (node (ref "Q5") (pin "1") (pintype "passive"))
      (node (ref "R18") (pin "1") (pintype "passive"))
      (node (ref "R22") (pin "2") (pintype "passive"))
    )
    (net (code "40") (name "Net-(Q5-Pad3)") (class "Default")
      (node (ref "Q5") (pin "3") (pintype "passive"))
      (node (ref "R14") (pin "1") (pintype "passive"))
    )
    (net (code "41") (name "Net-(U2-VUSB)") (class "Default")
      (node (ref "C10") (pin "1") (pinfunction "1_1") (pintype "passive"))
      (node (ref "U2") (pin "11") (pinfunction "VUSB_11") (pintype "power_in"))
    )
    (net (code "42") (name "Net-(U2-~{RST})") (class "Default")
      (node (ref "R10") (pin "2") (pintype "passive"))
      (node (ref "U2") (pin "4") (pinfunction "~{RST}_4") (pintype "input"))
    )
    (net (code "43") (name "Net-(U5-*FAULT)") (class "Default")
      (node (ref "R25") (pin "2") (pintype "passive"))
      (node (ref "U5") (pin "6") (pinfunction "*FAULT_6") (pintype "passive"))
    )
    (net (code "44") (name "Net-(U6-*FAULT)") (class "Default")
      (node (ref "R26") (pin "2") (pintype "passive"))
      (node (ref "U6") (pin "6") (pinfunction "*FAULT_6") (pintype "passive"))
    )
    (net (code "45") (name "SWCLK") (class "Default")
      (node (ref "J3") (pin "1") (pinfunction "1_1") (pintype "passive"))
      (node (ref "R8") (pin "1") (pintype "passive"))
      (node (ref "U1") (pin "49") (pinfunction "PA14_49") (pintype "bidirectional"))
    )
    (net (code "46") (name "SWDIO") (class "Default")
      (node (ref "J3") (pin "3") (pinfunction "3_3") (pintype "passive"))
      (node (ref "R9") (pin "2") (pintype "passive"))
      (node (ref "U1") (pin "46") (pinfunction "PA13_46") (pintype "bidirectional"))
    )
    (net (code "47") (name "UART_RX") (class "Default")
      (node (ref "J4") (pin "2") (pinfunction "2_2") (pintype "passive"))
      (node (ref "U1") (pin "17") (pinfunction "PA3_17") (pintype "bidirectional"))
      (node (ref "U2") (pin "5") (pinfunction "URX_5") (pintype "input"))
    )
    (net (code "48") (name "UART_TX") (class "Default")
      (node (ref "J4") (pin "1") (pinfunction "1_1") (pintype "passive"))
      (node (ref "U1") (pin "16") (pinfunction "PA2_16") (pintype "bidirectional"))
      (node (ref "U2") (pin "6") (pinfunction "UTX_6") (pintype "output"))
    )
    (net (code "49") (name "USB_D+") (class "Default")
      (node (ref "U2") (pin "13") (pinfunction "D+_13") (pintype "bidirectional"))
      (node (ref "U4") (pin "1") (pinfunction "D+O_1") (pintype "bidirectional"))
    )
    (net (code "50") (name "USB_D-") (class "Default")
      (node (ref "U2") (pin "12") (pinfunction "D-_12") (pintype "bidirectional"))
      (node (ref "U4") (pin "3") (pinfunction "D-O_3") (pintype "bidirectional"))
    )
    (net (code "51") (name "USB_D_N") (class "Default")
      (node (ref "J5") (pin "2") (pinfunction "D-_2") (pintype "passive"))
      (node (ref "U4") (pin "4") (pinfunction "D-I_4") (pintype "bidirectional"))
    )
    (net (code "52") (name "USB_D_P") (class "Default")
      (node (ref "J5") (pin "3") (pinfunction "D+_3") (pintype "passive"))
      (node (ref "U4") (pin "6") (pinfunction "D+I_6") (pintype "bidirectional"))
    )
    (net (code "53") (name "VBUS") (class "Default")
      (node (ref "C12") (pin "2") (pinfunction "2_2") (pintype "passive"))
      (node (ref "C9") (pin "1") (pinfunction "1_1") (pintype "passive"))
      (node (ref "L2") (pin "2") (pinfunction "2_2") (pintype "passive"))
      (node (ref "U2") (pin "1") (pinfunction "VDD_1") (pintype "power_in"))
      (node (ref "U3") (pin "3") (pinfunction "INPUT_3") (pintype "input"))
    )
    (net (code "54") (name "VDDA") (class "Default")
      (node (ref "C1") (pin "2") (pinfunction "2_2") (pintype "passive"))
      (node (ref "C2") (pin "2") (pinfunction "2_2") (pintype "passive"))
      (node (ref "L1") (pin "1") (pinfunction "1_1") (pintype "passive"))
      (node (ref "U1") (pin "13") (pinfunction "VDDA_13") (pintype "power_in"))
    )
    (net (code "55") (name "VOLT_SENSE_1_NEG") (class "Default")
      (node (ref "J11") (pin "1") (pintype "passive"))
      (node (ref "J18") (pin "2") (pinfunction "2_2") (pintype "passive"))
      (node (ref "J19") (pin "2") (pinfunction "2_2") (pintype "passive"))
      (node (ref "U8") (pin "5") (pinfunction "AIN1_5") (pintype "input"))
    )
    (net (code "56") (name "VOLT_SENSE_1_POS") (class "Default")
      (node (ref "J10") (pin "1") (pintype "passive"))
      (node (ref "U8") (pin "4") (pinfunction "AIN0_4") (pintype "input"))
    )
    (net (code "57") (name "VOLT_SENSE_2_NEG") (class "Default")
      (node (ref "J13") (pin "1") (pintype "passive"))
      (node (ref "J19") (pin "1") (pinfunction "1_1") (pintype "passive"))
      (node (ref "J20") (pin "1") (pinfunction "1_1") (pintype "passive"))
      (node (ref "U8") (pin "7") (pinfunction "AIN3_7") (pintype "input"))
    )
    (net (code "58") (name "VOLT_SENSE_2_POS") (class "Default")
      (node (ref "J12") (pin "1") (pintype "passive"))
      (node (ref "U8") (pin "6") (pinfunction "AIN2_6") (pintype "input"))
    )
    (net (code "59") (name "VOLT_SENSE_3_NEG") (class "Default")
      (node (ref "J15") (pin "1") (pintype "passive"))
      (node (ref "J18") (pin "1") (pinfunction "1_1") (pintype "passive"))
      (node (ref "J21") (pin "2") (pinfunction "2_2") (pintype "passive"))
      (node (ref "U9") (pin "5") (pinfunction "AIN1_5") (pintype "input"))
    )
    (net (code "60") (name "VOLT_SENSE_3_POS") (class "Default")
      (node (ref "J14") (pin "1") (pintype "passive"))
      (node (ref "U9") (pin "4") (pinfunction "AIN0_4") (pintype "input"))
    )
    (net (code "61") (name "VOLT_SENSE_4_NEG") (class "Default")
      (node (ref "J17") (pin "1") (pintype "passive"))
      (node (ref "J20") (pin "2") (pinfunction "2_2") (pintype "passive"))
      (node (ref "J21") (pin "1") (pinfunction "1_1") (pintype "passive"))
      (node (ref "U9") (pin "7") (pinfunction "AIN3_7") (pintype "input"))
    )
    (net (code "62") (name "VOLT_SENSE_4_POS") (class "Default")
      (node (ref "J16") (pin "1") (pintype "passive"))
      (node (ref "U9") (pin "6") (pinfunction "AIN2_6") (pintype "input"))
    )
    (net (code "63") (name "unconnected-(J5-ID-Pad4)") (class "Default")
      (node (ref "J5") (pin "4") (pinfunction "ID_4") (pintype "passive+no_connect"))
    )
    (net (code "64") (name "unconnected-(J5-SHIELD-PadS1)") (class "Default")
      (node (ref "J5") (pin "S1") (pinfunction "SHIELD_S1") (pintype "passive+no_connect"))
    )
    (net (code "65") (name "unconnected-(J5-SHIELD-PadS2)") (class "Default")
      (node (ref "J5") (pin "S2") (pinfunction "SHIELD_S2") (pintype "passive+no_connect"))
    )
    (net (code "66") (name "unconnected-(J5-SHIELD-PadS3)") (class "Default")
      (node (ref "J5") (pin "S3") (pinfunction "SHIELD_S3") (pintype "passive+no_connect"))
    )
    (net (code "67") (name "unconnected-(J5-SHIELD-PadS4)") (class "Default")
      (node (ref "J5") (pin "S4") (pinfunction "SHIELD_S4") (pintype "passive+no_connect"))
    )
    (net (code "68") (name "unconnected-(J5-SHIELD-PadS5)") (class "Default")
      (node (ref "J5") (pin "S5") (pinfunction "SHIELD_S5") (pintype "passive+no_connect"))
    )
    (net (code "69") (name "unconnected-(J5-SHIELD-PadS6)") (class "Default")
      (node (ref "J5") (pin "S6") (pinfunction "SHIELD_S6") (pintype "passive+no_connect"))
    )
    (net (code "70") (name "unconnected-(SW1-Pad3)") (class "Default")
      (node (ref "SW1") (pin "3") (pintype "passive"))
    )
    (net (code "71") (name "unconnected-(U1A-PA0-WKUP-Pad14)") (class "Default")
      (node (ref "U1") (pin "14") (pinfunction "PA0-WKUP_14") (pintype "bidirectional"))
    )
    (net (code "72") (name "unconnected-(U1A-PA1-Pad15)") (class "Default")
      (node (ref "U1") (pin "15") (pinfunction "PA1_15") (pintype "bidirectional"))
    )
    (net (code "73") (name "unconnected-(U1A-PA4-Pad20)") (class "Default")
      (node (ref "U1") (pin "20") (pinfunction "PA4_20") (pintype "bidirectional"))
    )
    (net (code "74") (name "unconnected-(U1A-PA6-Pad22)") (class "Default")
      (node (ref "U1") (pin "22") (pinfunction "PA6_22") (pintype "bidirectional"))
    )
    (net (code "75") (name "unconnected-(U1A-PA7-Pad23)") (class "Default")
      (node (ref "U1") (pin "23") (pinfunction "PA7_23") (pintype "bidirectional"))
    )
    (net (code "76") (name "unconnected-(U1A-PA8-Pad41)") (class "Default")
      (node (ref "U1") (pin "41") (pinfunction "PA8_41") (pintype "bidirectional"))
    )
    (net (code "77") (name "unconnected-(U1A-PA9-Pad42)") (class "Default")
      (node (ref "U1") (pin "42") (pinfunction "PA9_42") (pintype "bidirectional"))
    )
    (net (code "78") (name "unconnected-(U1A-PA10-Pad43)") (class "Default")
      (node (ref "U1") (pin "43") (pinfunction "PA10_43") (pintype "bidirectional"))
    )
    (net (code "79") (name "unconnected-(U1A-PA11-Pad44)") (class "Default")
      (node (ref "U1") (pin "44") (pinfunction "PA11_44") (pintype "bidirectional"))
    )
    (net (code "80") (name "unconnected-(U1A-PA12-Pad45)") (class "Default")
      (node (ref "U1") (pin "45") (pinfunction "PA12_45") (pintype "bidirectional"))
    )
    (net (code "81") (name "unconnected-(U1A-PA15-Pad50)") (class "Default")
      (node (ref "U1") (pin "50") (pinfunction "PA15_50") (pintype "bidirectional"))
    )
    (net (code "82") (name "unconnected-(U1A-PB0-Pad26)") (class "Default")
      (node (ref "U1") (pin "26") (pinfunction "PB0_26") (pintype "bidirectional"))
    )
    (net (code "83") (name "unconnected-(U1A-PB1-Pad27)") (class "Default")
      (node (ref "U1") (pin "27") (pinfunction "PB1_27") (pintype "bidirectional"))
    )
    (net (code "84") (name "unconnected-(U1A-PB3-Pad55)") (class "Default")
      (node (ref "U1") (pin "55") (pinfunction "PB3_55") (pintype "bidirectional"))
    )
    (net (code "85") (name "unconnected-(U1A-PB4-Pad56)") (class "Default")
      (node (ref "U1") (pin "56") (pinfunction "PB4_56") (pintype "bidirectional"))
    )
    (net (code "86") (name "unconnected-(U1A-PB5-Pad57)") (class "Default")
      (node (ref "U1") (pin "57") (pinfunction "PB5_57") (pintype "bidirectional"))
    )
    (net (code "87") (name "unconnected-(U1A-PB6-Pad58)") (class "Default")
      (node (ref "U1") (pin "58") (pinfunction "PB6_58") (pintype "bidirectional"))
    )
    (net (code "88") (name "unconnected-(U1A-PB7-Pad59)") (class "Default")
      (node (ref "U1") (pin "59") (pinfunction "PB7_59") (pintype "bidirectional"))
    )
    (net (code "89") (name "unconnected-(U1A-PB10-Pad29)") (class "Default")
      (node (ref "U1") (pin "29") (pinfunction "PB10_29") (pintype "bidirectional"))
    )
    (net (code "90") (name "unconnected-(U1A-PB11-Pad30)") (class "Default")
      (node (ref "U1") (pin "30") (pinfunction "PB11_30") (pintype "bidirectional"))
    )
    (net (code "91") (name "unconnected-(U1A-PB12-Pad33)") (class "Default")
      (node (ref "U1") (pin "33") (pinfunction "PB12_33") (pintype "bidirectional"))
    )
    (net (code "92") (name "unconnected-(U1A-PB13-Pad34)") (class "Default")
      (node (ref "U1") (pin "34") (pinfunction "PB13_34") (pintype "bidirectional"))
    )
    (net (code "93") (name "unconnected-(U1A-PB14-Pad35)") (class "Default")
      (node (ref "U1") (pin "35") (pinfunction "PB14_35") (pintype "bidirectional"))
    )
    (net (code "94") (name "unconnected-(U1A-PB15-Pad36)") (class "Default")
      (node (ref "U1") (pin "36") (pinfunction "PB15_36") (pintype "bidirectional"))
    )
    (net (code "95") (name "unconnected-(U1A-PC0-Pad8)") (class "Default")
      (node (ref "U1") (pin "8") (pinfunction "PC0_8") (pintype "bidirectional"))
    )
    (net (code "96") (name "unconnected-(U1A-PC1-Pad9)") (class "Default")
      (node (ref "U1") (pin "9") (pinfunction "PC1_9") (pintype "bidirectional"))
    )
    (net (code "97") (name "unconnected-(U1A-PC2-Pad10)") (class "Default")
      (node (ref "U1") (pin "10") (pinfunction "PC2_10") (pintype "bidirectional"))
    )
    (net (code "98") (name "unconnected-(U1A-PC3-Pad11)") (class "Default")
      (node (ref "U1") (pin "11") (pinfunction "PC3_11") (pintype "bidirectional"))
    )
    (net (code "99") (name "unconnected-(U1A-PC4-Pad24)") (class "Default")
      (node (ref "U1") (pin "24") (pinfunction "PC4_24") (pintype "bidirectional"))
    )
    (net (code "100") (name "unconnected-(U1A-PC5-Pad25)") (class "Default")
      (node (ref "U1") (pin "25") (pinfunction "PC5_25") (pintype "bidirectional"))
    )
    (net (code "101") (name "unconnected-(U1A-PC6-Pad37)") (class "Default")
      (node (ref "U1") (pin "37") (pinfunction "PC6_37") (pintype "bidirectional"))
    )
    (net (code "102") (name "unconnected-(U1A-PC7-Pad38)") (class "Default")
      (node (ref "U1") (pin "38") (pinfunction "PC7_38") (pintype "bidirectional"))
    )
    (net (code "103") (name "unconnected-(U1A-PC8-Pad39)") (class "Default")
      (node (ref "U1") (pin "39") (pinfunction "PC8_39") (pintype "bidirectional"))
    )
    (net (code "104") (name "unconnected-(U1A-PC9-Pad40)") (class "Default")
      (node (ref "U1") (pin "40") (pinfunction "PC9_40") (pintype "bidirectional"))
    )
    (net (code "105") (name "unconnected-(U1A-PC10-Pad51)") (class "Default")
      (node (ref "U1") (pin "51") (pinfunction "PC10_51") (pintype "bidirectional"))
    )
    (net (code "106") (name "unconnected-(U1A-PC11-Pad52)") (class "Default")
      (node (ref "U1") (pin "52") (pinfunction "PC11_52") (pintype "bidirectional"))
    )
    (net (code "107") (name "unconnected-(U1A-PC12-Pad53)") (class "Default")
      (node (ref "U1") (pin "53") (pinfunction "PC12_53") (pintype "bidirectional"))
    )
    (net (code "108") (name "unconnected-(U1A-PC13-TAMPER-RTC-Pad2)") (class "Default")
      (node (ref "U1") (pin "2") (pinfunction "PC13-TAMPER-RTC_2") (pintype "bidirectional"))
    )
    (net (code "109") (name "unconnected-(U1A-PC14-OSC32_IN-Pad3)") (class "Default")
      (node (ref "U1") (pin "3") (pinfunction "PC14-OSC32_IN_3") (pintype "bidirectional"))
    )
    (net (code "110") (name "unconnected-(U1A-PC15-OSC32_OUT-Pad4)") (class "Default")
      (node (ref "U1") (pin "4") (pinfunction "PC15-OSC32_OUT_4") (pintype "bidirectional"))
    )
    (net (code "111") (name "unconnected-(U1A-PD0-OSC_IN-Pad5)") (class "Default")
      (node (ref "U1") (pin "5") (pinfunction "PD0-OSC_IN_5") (pintype "bidirectional"))
    )
    (net (code "112") (name "unconnected-(U1A-PD1-OSC_OUT-Pad6)") (class "Default")
      (node (ref "U1") (pin "6") (pinfunction "PD1-OSC_OUT_6") (pintype "bidirectional"))
    )
    (net (code "113") (name "unconnected-(U1A-PD2-Pad54)") (class "Default")
      (node (ref "U1") (pin "54") (pinfunction "PD2_54") (pintype "bidirectional"))
    )
    (net (code "114") (name "unconnected-(U7-AIN2-Pad6)") (class "Default")
      (node (ref "U7") (pin "6") (pinfunction "AIN2_6") (pintype "input"))
    )
    (net (code "115") (name "unconnected-(U7-ALERT{slash}RDY-Pad2)") (class "Default")
      (node (ref "U7") (pin "2") (pinfunction "ALERT/RDY_2") (pintype "output"))
    )
    (net (code "116") (name "unconnected-(U8-ALERT{slash}RDY-Pad2)") (class "Default")
      (node (ref "U8") (pin "2") (pinfunction "ALERT/RDY_2") (pintype "output"))
    )
    (net (code "117") (name "unconnected-(U9-ALERT{slash}RDY-Pad2)") (class "Default")
      (node (ref "U9") (pin "2") (pinfunction "ALERT/RDY_2") (pintype "output"))
    )
  )
)
